# 21_-_AUDIO.net
KiCad netlist of a schematic drawn in Altium Designer
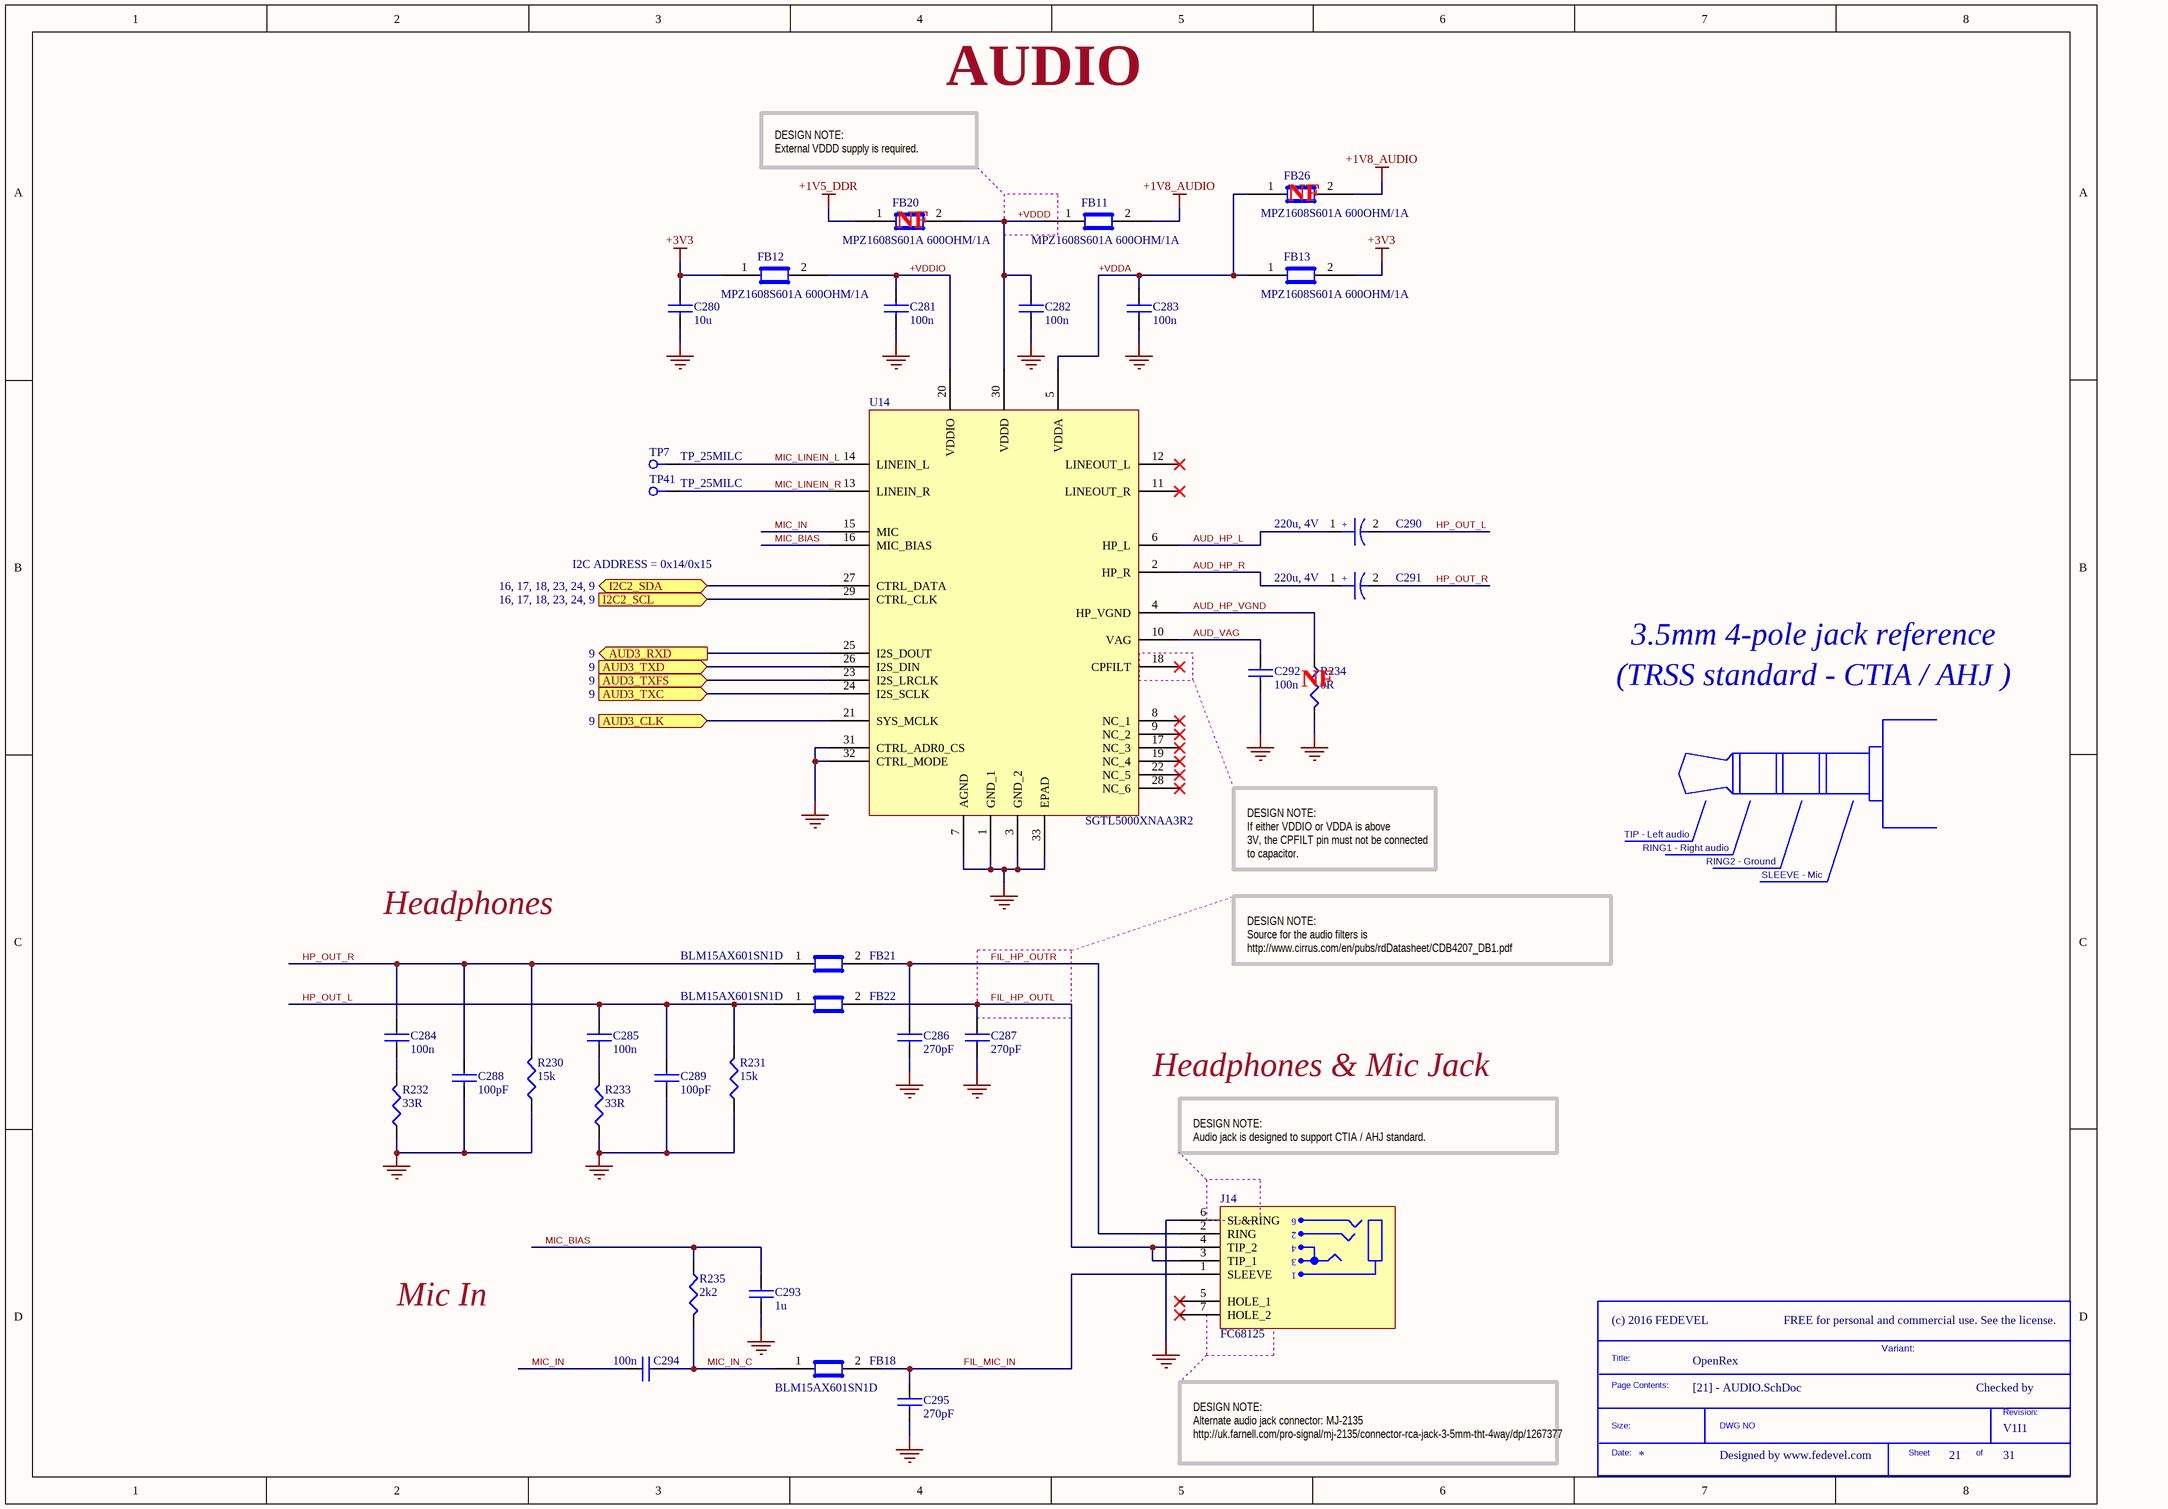
[diagram p0: [21] - AUDIO.SchDoc]

(export (version "E")
  (design (tool "Eeschema 10.0.6"))
  (components
    (comp (ref "C280")
      (value "10u")
      (footprint "C0603")
      (description "CAP CER 10UF 6.3V X5R 20% 0603")
      (fields
        (field (name "MANUFACTURER") "TDK Corporation")
        (field (name "MANUFACTURER PART NUMBER") "C1608X5R0J106M")
      )
      (libsource (lib "Integrated_Library_FEDEVEL_APR_2015") (part "C1608X5R0J106M"))
    )
    (comp (ref "C281")
      (value "100n")
      (footprint "C0402")
      (description "CAP CER .10UF 50V X5R 10% 0402")
      (fields
        (field (name "MANUFACTURER") "TDK Corporation")
        (field (name "MANUFACTURER PART NUMBER") "C1005X5R1H104K")
      )
      (libsource (lib "Integrated_Library_FEDEVEL_APR_2015") (part "C1005X5R1H104K"))
    )
    (comp (ref "C282")
      (value "100n")
      (footprint "C0402")
      (description "CAP CER .10UF 50V X5R 10% 0402")
      (fields
        (field (name "MANUFACTURER") "TDK Corporation")
        (field (name "MANUFACTURER PART NUMBER") "C1005X5R1H104K")
      )
      (libsource (lib "Integrated_Library_FEDEVEL_APR_2015") (part "C1005X5R1H104K"))
    )
    (comp (ref "C283")
      (value "100n")
      (footprint "C0402")
      (description "CAP CER .10UF 50V X5R 10% 0402")
      (fields
        (field (name "MANUFACTURER") "TDK Corporation")
        (field (name "MANUFACTURER PART NUMBER") "C1005X5R1H104K")
      )
      (libsource (lib "Integrated_Library_FEDEVEL_APR_2015") (part "C1005X5R1H104K"))
    )
    (comp (ref "C284")
      (value "100n")
      (footprint "C0402")
      (description "CAP CER .10UF 50V X5R 10% 0402")
      (fields
        (field (name "MANUFACTURER") "TDK Corporation")
        (field (name "MANUFACTURER PART NUMBER") "C1005X5R1H104K")
      )
      (libsource (lib "Integrated_Library_FEDEVEL_APR_2015") (part "C1005X5R1H104K"))
    )
    (comp (ref "C285")
      (value "100n")
      (footprint "C0402")
      (description "CAP CER .10UF 50V X5R 10% 0402")
      (fields
        (field (name "MANUFACTURER") "TDK Corporation")
        (field (name "MANUFACTURER PART NUMBER") "C1005X5R1H104K")
      )
      (libsource (lib "Integrated_Library_FEDEVEL_APR_2015") (part "C1005X5R1H104K"))
    )
    (comp (ref "C286")
      (value "270pF")
      (footprint "C0402")
      (description "CAP CER 270PF 50V 10% X7R 0402")
      (fields
        (field (name "MANUFACTURER") "Murata Electronics North America")
        (field (name "MANUFACTURER PART NUMBER") "GRM155R71H271KA01D")
      )
      (libsource (lib "Integrated_Library_FEDEVEL_APR_2015") (part "GRM155R71H271KA01D"))
    )
    (comp (ref "C287")
      (value "270pF")
      (footprint "C0402")
      (description "CAP CER 270PF 50V 10% X7R 0402")
      (fields
        (field (name "MANUFACTURER") "Murata Electronics North America")
        (field (name "MANUFACTURER PART NUMBER") "GRM155R71H271KA01D")
      )
      (libsource (lib "Integrated_Library_FEDEVEL_APR_2015") (part "GRM155R71H271KA01D"))
    )
    (comp (ref "C288")
      (value "100pF")
      (footprint "C0402")
      (description "CAP CER 100PF 50V 5% NP0 0402")
      (fields
        (field (name "MANUFACTURER") "TDK Corporation")
        (field (name "MANUFACTURER PART NUMBER") "C1005C0G1H101J")
      )
      (libsource (lib "Integrated_Library_FEDEVEL_APR_2015") (part "C1005C0G1H101J"))
    )
    (comp (ref "C289")
      (value "100pF")
      (footprint "C0402")
      (description "CAP CER 100PF 50V 5% NP0 0402")
      (fields
        (field (name "MANUFACTURER") "TDK Corporation")
        (field (name "MANUFACTURER PART NUMBER") "C1005C0G1H101J")
      )
      (libsource (lib "Integrated_Library_FEDEVEL_APR_2015") (part "C1005C0G1H101J"))
    )
    (comp (ref "C290")
      (value "220u, 4V")
      (footprint "C1206 -  TLN S Case Tantal")
      (description "CAP TANT 220UF 4V 20% 1206")
      (fields
        (field (name "MANUFACTURER") "AVX Corporation")
        (field (name "MANUFACTURER PART NUMBER") "TLNS227M004R3000")
      )
      (libsource (lib "Integrated_Library_FEDEVEL_APR_2015") (part "TLNS227M004R3000"))
    )
    (comp (ref "C291")
      (value "220u, 4V")
      (footprint "C1206 -  TLN S Case Tantal")
      (description "CAP TANT 220UF 4V 20% 1206")
      (fields
        (field (name "MANUFACTURER") "AVX Corporation")
        (field (name "MANUFACTURER PART NUMBER") "TLNS227M004R3000")
      )
      (libsource (lib "Integrated_Library_FEDEVEL_APR_2015") (part "TLNS227M004R3000"))
    )
    (comp (ref "C292")
      (value "100n")
      (footprint "C0402")
      (description "CAP CER .10UF 50V X5R 10% 0402")
      (fields
        (field (name "MANUFACTURER") "TDK Corporation")
        (field (name "MANUFACTURER PART NUMBER") "C1005X5R1H104K")
      )
      (libsource (lib "Integrated_Library_FEDEVEL_APR_2015") (part "C1005X5R1H104K"))
    )
    (comp (ref "C293")
      (value "1u")
      (footprint "C0402")
      (description "CAP CER 1.0UF 16V X5R 0402")
      (fields
        (field (name "MANUFACTURER") "TDK Corporation")
        (field (name "MANUFACTURER PART NUMBER") "C1005X5R1C105K")
      )
      (libsource (lib "Integrated_Library_FEDEVEL_APR_2015") (part "C1005X5R1C105K"))
    )
    (comp (ref "C294")
      (value "100n")
      (footprint "C0402")
      (description "CAP CER .10UF 50V X5R 10% 0402")
      (fields
        (field (name "MANUFACTURER") "TDK Corporation")
        (field (name "MANUFACTURER PART NUMBER") "C1005X5R1H104K")
      )
      (libsource (lib "Integrated_Library_FEDEVEL_APR_2015") (part "C1005X5R1H104K"))
    )
    (comp (ref "C295")
      (value "270pF")
      (footprint "C0402")
      (description "CAP CER 270PF 50V 10% X7R 0402")
      (fields
        (field (name "MANUFACTURER") "Murata Electronics North America")
        (field (name "MANUFACTURER PART NUMBER") "GRM155R71H271KA01D")
      )
      (libsource (lib "Integrated_Library_FEDEVEL_APR_2015") (part "GRM155R71H271KA01D"))
    )
    (comp (ref "FB11")
      (value "MPZ1608S601A 600OHM/1A")
      (footprint "C0603")
      (description "FERRITE CHIP BEAD 600 OHM SMD 1A")
      (fields
        (field (name "MANUFACTURER") "TDK Corporation")
        (field (name "MANUFACTURER PART NUMBER") "MPZ1608S601A")
      )
      (libsource (lib "Integrated_Library_FEDEVEL_APR_2015") (part "MPZ1608S601A"))
    )
    (comp (ref "FB12")
      (value "MPZ1608S601A 600OHM/1A")
      (footprint "C0603")
      (description "FERRITE CHIP BEAD 600 OHM SMD 1A")
      (fields
        (field (name "MANUFACTURER") "TDK Corporation")
        (field (name "MANUFACTURER PART NUMBER") "MPZ1608S601A")
      )
      (libsource (lib "Integrated_Library_FEDEVEL_APR_2015") (part "MPZ1608S601A"))
    )
    (comp (ref "FB13")
      (value "MPZ1608S601A 600OHM/1A")
      (footprint "C0603")
      (description "FERRITE CHIP BEAD 600 OHM SMD 1A")
      (fields
        (field (name "MANUFACTURER") "TDK Corporation")
        (field (name "MANUFACTURER PART NUMBER") "MPZ1608S601A")
      )
      (libsource (lib "Integrated_Library_FEDEVEL_APR_2015") (part "MPZ1608S601A"))
    )
    (comp (ref "FB18")
      (value "BLM15AX601SN1D")
      (footprint "C0402")
      (description "FERRITE CHIP 600 OHM 0402 420mA")
      (fields (field (name "MANUFACTURER") "Murata Electronics North America"))
      (libsource (lib "Integrated_Library_FEDEVEL_APR_2015") (part "BLM15AX601SN1D"))
    )
    (comp (ref "FB20")
      (value "MPZ1608S601A 600OHM/1A")
      (footprint "C0603")
      (description "FERRITE CHIP BEAD 600 OHM SMD 1A")
      (fields
        (field (name "MANUFACTURER") "TDK Corporation")
        (field (name "MANUFACTURER PART NUMBER") "MPZ1608S601A")
      )
      (libsource (lib "Integrated_Library_FEDEVEL_APR_2015") (part "MPZ1608S601A"))
    )
    (comp (ref "FB21")
      (value "BLM15AX601SN1D")
      (footprint "C0402")
      (description "FERRITE CHIP 600 OHM 0402 420mA")
      (fields (field (name "MANUFACTURER") "Murata Electronics North America"))
      (libsource (lib "Integrated_Library_FEDEVEL_APR_2015") (part "BLM15AX601SN1D"))
    )
    (comp (ref "FB22")
      (value "BLM15AX601SN1D")
      (footprint "C0402")
      (description "FERRITE CHIP 600 OHM 0402 420mA")
      (fields (field (name "MANUFACTURER") "Murata Electronics North America"))
      (libsource (lib "Integrated_Library_FEDEVEL_APR_2015") (part "BLM15AX601SN1D"))
    )
    (comp (ref "FB26")
      (value "MPZ1608S601A 600OHM/1A")
      (footprint "C0603")
      (description "FERRITE CHIP BEAD 600 OHM SMD 1A")
      (fields
        (field (name "MANUFACTURER") "TDK Corporation")
        (field (name "MANUFACTURER PART NUMBER") "MPZ1608S601A")
      )
      (libsource (lib "Integrated_Library_FEDEVEL_APR_2015") (part "MPZ1608S601A"))
    )
    (comp (ref "J14")
      (value "FC68125")
      (footprint "FC68125")
      (description "CLIFF ELECTRONIC COMPONENTS - FC68125 - CONNECTOR, PHONO, 3.5MM, JACK, 4POLE")
      (fields
        (field (name "MANUFACTURER") "CLIFF ELECTRONIC COMPONENTS")
        (field (name ".CREATOR") "MM")
        (field (name ".CHECKED PCB") "MM")
        (field (name ".CHECKED SCH") "MM")
      )
      (libsource (lib "Integrated_Library_FEDEVEL_APR_2015") (part "FC68125"))
    )
    (comp (ref "R230")
      (value "15k")
      (footprint "R0402")
      (description "RES 15.0K OHM 1/16W 1% 0402 SMD")
      (fields
        (field (name "MANUFACTURER") "Yageo")
        (field (name "MANUFACTURER PART NUMBER") "RC0402FR-0715KL")
      )
      (libsource (lib "Integrated_Library_FEDEVEL_APR_2015") (part "RC0402FR-0715KL"))
    )
    (comp (ref "R231")
      (value "15k")
      (footprint "R0402")
      (description "RES 15.0K OHM 1/16W 1% 0402 SMD")
      (fields
        (field (name "MANUFACTURER") "Yageo")
        (field (name "MANUFACTURER PART NUMBER") "RC0402FR-0715KL")
      )
      (libsource (lib "Integrated_Library_FEDEVEL_APR_2015") (part "RC0402FR-0715KL"))
    )
    (comp (ref "R232")
      (value "33R")
      (footprint "R0402")
      (description "RES TF 33 OHM 1% 1/16W 0402")
      (fields
        (field (name "MANUFACTURER") "Stackpole Electronics Inc")
        (field (name "MANUFACTURER PART NUMBER") "RMCF0402FT33R0")
      )
      (libsource (lib "Integrated_Library_FEDEVEL_APR_2015") (part "RMCF0402FT33R0"))
    )
    (comp (ref "R233")
      (value "33R")
      (footprint "R0402")
      (description "RES TF 33 OHM 1% 1/16W 0402")
      (fields
        (field (name "MANUFACTURER") "Stackpole Electronics Inc")
        (field (name "MANUFACTURER PART NUMBER") "RMCF0402FT33R0")
      )
      (libsource (lib "Integrated_Library_FEDEVEL_APR_2015") (part "RMCF0402FT33R0"))
    )
    (comp (ref "R234")
      (value "0R")
      (footprint "R0402")
      (description "RES 0.0 OHM 1/16W 0402 SMD")
      (fields
        (field (name "MANUFACTURER") "Yageo")
        (field (name "MANUFACTURER PART NUMBER") "RC0402JR-070RL")
      )
      (libsource (lib "Integrated_Library_FEDEVEL_APR_2015") (part "RC0402JR-070RL"))
    )
    (comp (ref "R235")
      (value "2k2")
      (footprint "R0402")
      (description "RES 2.20K OHM 1/16W 1% 0402 SMD")
      (fields
        (field (name "MANUFACTURER") "Yageo")
        (field (name "MANUFACTURER PART NUMBER") "RC0402FR-072K2L")
      )
      (libsource (lib "Integrated_Library_FEDEVEL_APR_2015") (part "RC0402FR-072K2L"))
    )
    (comp (ref "TP7")
      (value "TP_25MILC")
      (footprint "TP_25C")
      (description "Test Point 25mil")
      (libsource (lib "Integrated_Library_FEDEVEL_APR_2015") (part "TP_25MILC"))
    )
    (comp (ref "TP41")
      (value "TP_25MILC")
      (footprint "TP_25C")
      (description "Test Point 25mil")
      (libsource (lib "Integrated_Library_FEDEVEL_APR_2015") (part "TP_25MILC"))
    )
    (comp (ref "U14")
      (value "SGTL5000XNAA3R2")
      (footprint "QFN32 5x5x0.85_V1.1")
      (description "IC AUDIO CODEC STEREO 32-QFN")
      (fields (field (name "MANUFACTURER") "Freescale Semiconductor") (field (name ".CREATOR") "MM"))
      (libsource (lib "Integrated_Library_FEDEVEL_APR_2015") (part "SGTL5000XNAA3R2"))
    )
  )
  (nets
    (net (code "1") (name "+1V5_DDR") (class "Default")
      (node (ref "FB20") (pin "1") (pinfunction "1_1") (pintype "passive"))
    )
    (net (code "2") (name "+1V8_AUDIO") (class "Default")
      (node (ref "FB11") (pin "2") (pinfunction "2_2") (pintype "passive"))
      (node (ref "FB26") (pin "2") (pinfunction "2_2") (pintype "passive"))
    )
    (net (code "3") (name "+3V3") (class "Default")
      (node (ref "C280") (pin "1") (pinfunction "1_1") (pintype "passive"))
      (node (ref "FB12") (pin "1") (pinfunction "1_1") (pintype "passive"))
      (node (ref "FB13") (pin "2") (pinfunction "2_2") (pintype "passive"))
    )
    (net (code "4") (name "/+VDDA") (class "Default")
      (node (ref "C283") (pin "1") (pinfunction "1_1") (pintype "passive"))
      (node (ref "FB13") (pin "1") (pinfunction "1_1") (pintype "passive"))
      (node (ref "FB26") (pin "1") (pinfunction "1_1") (pintype "passive"))
      (node (ref "U14") (pin "5") (pinfunction "VDDA_5") (pintype "passive"))
    )
    (net (code "5") (name "/+VDDD") (class "Default")
      (node (ref "C282") (pin "1") (pinfunction "1_1") (pintype "passive"))
      (node (ref "FB11") (pin "1") (pinfunction "1_1") (pintype "passive"))
      (node (ref "FB20") (pin "2") (pinfunction "2_2") (pintype "passive"))
      (node (ref "U14") (pin "30") (pinfunction "VDDD_30") (pintype "passive"))
    )
    (net (code "6") (name "/+VDDIO") (class "Default")
      (node (ref "C281") (pin "1") (pinfunction "1_1") (pintype "passive"))
      (node (ref "FB12") (pin "2") (pinfunction "2_2") (pintype "passive"))
      (node (ref "U14") (pin "20") (pinfunction "VDDIO_20") (pintype "passive"))
    )
    (net (code "7") (name "/AUD3_CLK") (class "Default")
      (node (ref "U14") (pin "21") (pinfunction "SYS_MCLK_21") (pintype "passive"))
    )
    (net (code "8") (name "/AUD3_RXD") (class "Default")
      (node (ref "U14") (pin "25") (pinfunction "I2S_DOUT_25") (pintype "passive"))
    )
    (net (code "9") (name "/AUD3_TXC") (class "Default")
      (node (ref "U14") (pin "24") (pinfunction "I2S_SCLK_24") (pintype "passive"))
    )
    (net (code "10") (name "/AUD3_TXD") (class "Default")
      (node (ref "U14") (pin "26") (pinfunction "I2S_DIN_26") (pintype "passive"))
    )
    (net (code "11") (name "/AUD3_TXFS") (class "Default")
      (node (ref "U14") (pin "23") (pinfunction "I2S_LRCLK_23") (pintype "passive"))
    )
    (net (code "12") (name "/AUD_HP_L") (class "Default")
      (node (ref "C290") (pin "1") (pinfunction "1_1") (pintype "passive"))
      (node (ref "U14") (pin "6") (pinfunction "HP_L_6") (pintype "passive"))
    )
    (net (code "13") (name "/AUD_HP_R") (class "Default")
      (node (ref "C291") (pin "1") (pinfunction "1_1") (pintype "passive"))
      (node (ref "U14") (pin "2") (pinfunction "HP_R_2") (pintype "passive"))
    )
    (net (code "14") (name "/AUD_HP_VGND") (class "Default")
      (node (ref "R234") (pin "1") (pinfunction "1_1") (pintype "passive"))
      (node (ref "U14") (pin "4") (pinfunction "HP_VGND_4") (pintype "passive"))
    )
    (net (code "15") (name "/AUD_VAG") (class "Default")
      (node (ref "C292") (pin "1") (pinfunction "1_1") (pintype "passive"))
      (node (ref "U14") (pin "10") (pinfunction "VAG_10") (pintype "passive"))
    )
    (net (code "16") (name "/FIL_HP_OUTL") (class "Default")
      (node (ref "C287") (pin "1") (pinfunction "1_1") (pintype "passive"))
      (node (ref "FB22") (pin "2") (pinfunction "2_2") (pintype "passive"))
      (node (ref "J14") (pin "3") (pinfunction "TIP_1_3") (pintype "passive"))
      (node (ref "J14") (pin "4") (pinfunction "TIP_2_4") (pintype "passive"))
    )
    (net (code "17") (name "/FIL_HP_OUTR") (class "Default")
      (node (ref "C286") (pin "1") (pinfunction "1_1") (pintype "passive"))
      (node (ref "FB21") (pin "2") (pinfunction "2_2") (pintype "passive"))
      (node (ref "J14") (pin "2") (pinfunction "RING_2") (pintype "passive"))
    )
    (net (code "18") (name "/FIL_MIC_IN") (class "Default")
      (node (ref "C295") (pin "1") (pinfunction "1_1") (pintype "passive"))
      (node (ref "FB18") (pin "2") (pinfunction "2_2") (pintype "passive"))
      (node (ref "J14") (pin "1") (pinfunction "SLEEVE_1") (pintype "passive"))
    )
    (net (code "19") (name "/HP_OUT_L") (class "Default")
      (node (ref "C285") (pin "1") (pinfunction "1_1") (pintype "passive"))
      (node (ref "C289") (pin "1") (pinfunction "1_1") (pintype "passive"))
      (node (ref "C290") (pin "2") (pinfunction "2_2") (pintype "passive"))
      (node (ref "FB22") (pin "1") (pinfunction "1_1") (pintype "passive"))
      (node (ref "R231") (pin "2") (pinfunction "2_2") (pintype "passive"))
    )
    (net (code "20") (name "/HP_OUT_R") (class "Default")
      (node (ref "C284") (pin "1") (pinfunction "1_1") (pintype "passive"))
      (node (ref "C288") (pin "1") (pinfunction "1_1") (pintype "passive"))
      (node (ref "C291") (pin "2") (pinfunction "2_2") (pintype "passive"))
      (node (ref "FB21") (pin "1") (pinfunction "1_1") (pintype "passive"))
      (node (ref "R230") (pin "2") (pinfunction "2_2") (pintype "passive"))
    )
    (net (code "21") (name "/I2C2_SCL") (class "Default")
      (node (ref "U14") (pin "29") (pinfunction "CTRL_CLK_29") (pintype "passive"))
    )
    (net (code "22") (name "/I2C2_SDA") (class "Default")
      (node (ref "U14") (pin "27") (pinfunction "CTRL_DATA_27") (pintype "passive"))
    )
    (net (code "23") (name "/MIC_BIAS") (class "Default")
      (node (ref "C293") (pin "1") (pinfunction "1_1") (pintype "passive"))
      (node (ref "R235") (pin "1") (pinfunction "1_1") (pintype "passive"))
      (node (ref "U14") (pin "16") (pinfunction "MIC_BIAS_16") (pintype "passive"))
    )
    (net (code "24") (name "/MIC_IN") (class "Default")
      (node (ref "C294") (pin "1") (pinfunction "1_1") (pintype "passive"))
      (node (ref "U14") (pin "15") (pinfunction "MIC_15") (pintype "passive"))
    )
    (net (code "25") (name "/MIC_IN_C") (class "Default")
      (node (ref "C294") (pin "2") (pinfunction "2_2") (pintype "passive"))
      (node (ref "FB18") (pin "1") (pinfunction "1_1") (pintype "passive"))
      (node (ref "R235") (pin "2") (pinfunction "2_2") (pintype "passive"))
    )
    (net (code "26") (name "/MIC_LINEIN_L") (class "Default")
      (node (ref "TP7") (pin "1") (pinfunction "1_1") (pintype "passive"))
      (node (ref "U14") (pin "14") (pinfunction "LINEIN_L_14") (pintype "passive"))
    )
    (net (code "27") (name "/MIC_LINEIN_R") (class "Default")
      (node (ref "TP41") (pin "1") (pinfunction "1_1") (pintype "passive"))
      (node (ref "U14") (pin "13") (pinfunction "LINEIN_R_13") (pintype "passive"))
    )
    (net (code "28") (name "GND") (class "Default")
      (node (ref "C280") (pin "2") (pinfunction "2_2") (pintype "passive"))
      (node (ref "C281") (pin "2") (pinfunction "2_2") (pintype "passive"))
      (node (ref "C282") (pin "2") (pinfunction "2_2") (pintype "passive"))
      (node (ref "C283") (pin "2") (pinfunction "2_2") (pintype "passive"))
      (node (ref "C286") (pin "2") (pinfunction "2_2") (pintype "passive"))
      (node (ref "C287") (pin "2") (pinfunction "2_2") (pintype "passive"))
      (node (ref "C288") (pin "2") (pinfunction "2_2") (pintype "passive"))
      (node (ref "C289") (pin "2") (pinfunction "2_2") (pintype "passive"))
      (node (ref "C292") (pin "2") (pinfunction "2_2") (pintype "passive"))
      (node (ref "C293") (pin "2") (pinfunction "2_2") (pintype "passive"))
      (node (ref "C295") (pin "2") (pinfunction "2_2") (pintype "passive"))
      (node (ref "J14") (pin "6") (pinfunction "SL&RING_6") (pintype "passive"))
      (node (ref "R230") (pin "1") (pinfunction "1_1") (pintype "passive"))
      (node (ref "R231") (pin "1") (pinfunction "1_1") (pintype "passive"))
      (node (ref "R232") (pin "1") (pinfunction "1_1") (pintype "passive"))
      (node (ref "R233") (pin "1") (pinfunction "1_1") (pintype "passive"))
      (node (ref "R234") (pin "2") (pinfunction "2_2") (pintype "passive"))
      (node (ref "U14") (pin "1") (pinfunction "GND_1_1") (pintype "passive"))
      (node (ref "U14") (pin "3") (pinfunction "GND_2_3") (pintype "passive"))
      (node (ref "U14") (pin "31") (pinfunction "CTRL_ADR0_CS_31") (pintype "passive"))
      (node (ref "U14") (pin "32") (pinfunction "CTRL_MODE_32") (pintype "passive"))
      (node (ref "U14") (pin "33") (pinfunction "EPAD_33") (pintype "passive"))
      (node (ref "U14") (pin "7") (pinfunction "AGND_7") (pintype "passive"))
    )
    (net (code "29") (name "Net-(C284-Pad2)") (class "Default")
      (node (ref "C284") (pin "2") (pinfunction "2_2") (pintype "passive"))
      (node (ref "R232") (pin "2") (pinfunction "2_2") (pintype "passive"))
    )
    (net (code "30") (name "Net-(C285-Pad2)") (class "Default")
      (node (ref "C285") (pin "2") (pinfunction "2_2") (pintype "passive"))
      (node (ref "R233") (pin "2") (pinfunction "2_2") (pintype "passive"))
    )
    (net (code "31") (name "unconnected-(J14-HOLE_1-Pad5)") (class "Default")
      (node (ref "J14") (pin "5") (pinfunction "HOLE_1_5") (pintype "passive+no_connect"))
    )
    (net (code "32") (name "unconnected-(J14-HOLE_2-Pad7)") (class "Default")
      (node (ref "J14") (pin "7") (pinfunction "HOLE_2_7") (pintype "passive+no_connect"))
    )
    (net (code "33") (name "unconnected-(U14-CPFILT-Pad18)") (class "Default")
      (node (ref "U14") (pin "18") (pinfunction "CPFILT_18") (pintype "passive+no_connect"))
    )
    (net (code "34") (name "unconnected-(U14-LINEOUT_L-Pad12)") (class "Default")
      (node (ref "U14") (pin "12") (pinfunction "LINEOUT_L_12") (pintype "passive+no_connect"))
    )
    (net (code "35") (name "unconnected-(U14-LINEOUT_R-Pad11)") (class "Default")
      (node (ref "U14") (pin "11") (pinfunction "LINEOUT_R_11") (pintype "passive+no_connect"))
    )
    (net (code "36") (name "unconnected-(U14-NC_1-Pad8)") (class "Default")
      (node (ref "U14") (pin "8") (pinfunction "NC_1_8") (pintype "passive+no_connect"))
    )
    (net (code "37") (name "unconnected-(U14-NC_2-Pad9)") (class "Default")
      (node (ref "U14") (pin "9") (pinfunction "NC_2_9") (pintype "passive+no_connect"))
    )
    (net (code "38") (name "unconnected-(U14-NC_3-Pad17)") (class "Default")
      (node (ref "U14") (pin "17") (pinfunction "NC_3_17") (pintype "passive+no_connect"))
    )
    (net (code "39") (name "unconnected-(U14-NC_4-Pad19)") (class "Default")
      (node (ref "U14") (pin "19") (pinfunction "NC_4_19") (pintype "passive+no_connect"))
    )
    (net (code "40") (name "unconnected-(U14-NC_5-Pad22)") (class "Default")
      (node (ref "U14") (pin "22") (pinfunction "NC_5_22") (pintype "passive+no_connect"))
    )
    (net (code "41") (name "unconnected-(U14-NC_6-Pad28)") (class "Default")
      (node (ref "U14") (pin "28") (pinfunction "NC_6_28") (pintype "passive+no_connect"))
    )
  )
)
